# Port_Headers.net
KiCad netlist of a schematic drawn in Altium Designer
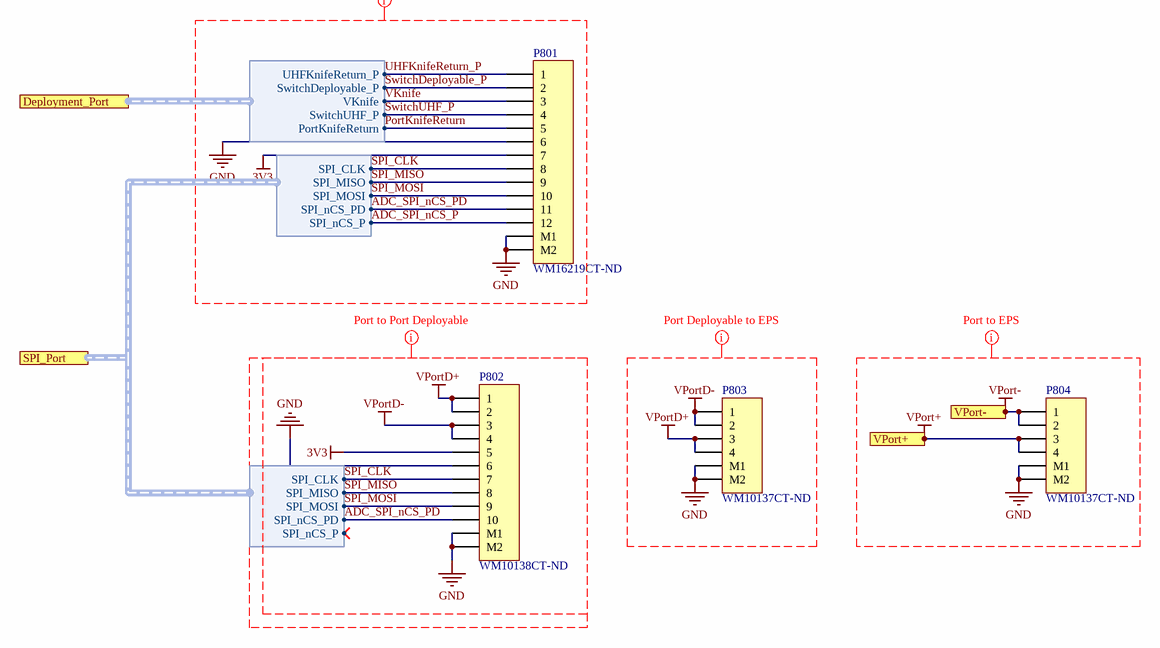
[diagram p0: Port_Headers.SchDoc]

(export (version "E")
  (design (tool "Eeschema 10.0.6"))
  (components
    (comp (ref "P801")
      (value "WM16219CT-ND")
      (footprint "MOLX-5040501291")
      (description "CONN HEADER SMD R/A 12POS 1.5MM")
      (fields
        (field (name "PART NUMBER") "71")
        (field (name "MANUFACTURER PART NUMBER") "5040501291")
        (field (name "PUBLISHER") "Altium Limited")
      )
      (libsource (lib "Database") (part "Header 14"))
    )
    (comp (ref "P802")
      (value "WM10138CT-ND")
      (footprint "MOLX-5040501091")
      (description "CONN HEADER SMD R/A 10POS 1.5MM")
      (fields
        (field (name "PART NUMBER") "69")
        (field (name "MANUFACTURER PART NUMBER") "5040501091")
        (field (name "PUBLISHER") "Altium Limited")
      )
      (libsource (lib "Database") (part "Header 12"))
    )
    (comp (ref "P803")
      (value "WM10137CT-ND")
      (footprint "MOLX-5040500491")
      (description "CONN HEADER SMD R/A 4POS 1.5MM")
      (fields
        (field (name "PART NUMBER") "63")
        (field (name "MANUFACTURER PART NUMBER") "5040500491")
        (field (name "PUBLISHER") "Altium Limited")
      )
      (libsource (lib "Database") (part "Header 6"))
    )
    (comp (ref "P804")
      (value "WM10137CT-ND")
      (footprint "MOLX-5040500491")
      (description "CONN HEADER SMD R/A 4POS 1.5MM")
      (fields
        (field (name "PART NUMBER") "63")
        (field (name "MANUFACTURER PART NUMBER") "5040500491")
        (field (name "PUBLISHER") "Altium Limited")
      )
      (libsource (lib "Database") (part "Header 6"))
    )
  )
  (nets
    (net (code "3") (name "/ADC_SPI_nCS_P") (class "Default")
      (node (ref "P801") (pin "12") (pinfunction "12_12") (pintype "passive"))
    )
    (net (code "4") (name "/ADC_SPI_nCS_PD") (class "Default")
      (node (ref "P801") (pin "11") (pinfunction "11_11") (pintype "passive"))
      (node (ref "P802") (pin "10") (pinfunction "10_10") (pintype "passive"))
    )
    (net (code "5") (name "/PortKnifeReturn") (class "Default")
      (node (ref "P801") (pin "5") (pinfunction "5_5") (pintype "passive"))
    )
    (net (code "6") (name "/SPI_CLK") (class "Default")
      (node (ref "P801") (pin "8") (pinfunction "8_8") (pintype "passive"))
      (node (ref "P802") (pin "7") (pinfunction "7_7") (pintype "passive"))
    )
    (net (code "7") (name "/SPI_MISO") (class "Default")
      (node (ref "P801") (pin "9") (pinfunction "9_9") (pintype "passive"))
      (node (ref "P802") (pin "8") (pinfunction "8_8") (pintype "passive"))
    )
    (net (code "8") (name "/SPI_MOSI") (class "Default")
      (node (ref "P801") (pin "10") (pinfunction "10_10") (pintype "passive"))
      (node (ref "P802") (pin "9") (pinfunction "9_9") (pintype "passive"))
    )
    (net (code "9") (name "/SwitchDeployable_P") (class "Default")
      (node (ref "P801") (pin "2") (pinfunction "2_2") (pintype "passive"))
    )
    (net (code "10") (name "/SwitchUHF_P") (class "Default")
      (node (ref "P801") (pin "4") (pinfunction "4_4") (pintype "passive"))
    )
    (net (code "11") (name "/UHFKnifeReturn_P") (class "Default")
      (node (ref "P801") (pin "1") (pinfunction "1_1") (pintype "passive"))
    )
    (net (code "12") (name "/VKnife") (class "Default")
      (node (ref "P801") (pin "3") (pinfunction "3_3") (pintype "passive"))
    )
    (net (code "15") (name "3V3") (class "Default")
      (node (ref "P801") (pin "7") (pinfunction "7_7") (pintype "passive"))
      (node (ref "P802") (pin "5") (pinfunction "5_5") (pintype "passive"))
    )
    (net (code "16") (name "GND") (class "Default")
      (node (ref "P801") (pin "6") (pinfunction "6_6") (pintype "passive"))
      (node (ref "P801") (pin "M1") (pinfunction "M1_M1") (pintype "passive"))
      (node (ref "P801") (pin "M2") (pinfunction "M2_M2") (pintype "passive"))
      (node (ref "P802") (pin "6") (pinfunction "6_6") (pintype "passive"))
      (node (ref "P802") (pin "M1") (pinfunction "M1_M1") (pintype "passive"))
      (node (ref "P802") (pin "M2") (pinfunction "M2_M2") (pintype "passive"))
      (node (ref "P803") (pin "M1") (pinfunction "M1_M1") (pintype "passive"))
      (node (ref "P803") (pin "M2") (pinfunction "M2_M2") (pintype "passive"))
      (node (ref "P804") (pin "M1") (pinfunction "M1_M1") (pintype "passive"))
      (node (ref "P804") (pin "M2") (pinfunction "M2_M2") (pintype "passive"))
    )
    (net (code "17") (name "VPort+") (class "Default")
      (node (ref "P804") (pin "3") (pinfunction "3_3") (pintype "passive"))
      (node (ref "P804") (pin "4") (pinfunction "4_4") (pintype "passive"))
    )
    (net (code "18") (name "VPort-") (class "Default")
      (node (ref "P804") (pin "1") (pinfunction "1_1") (pintype "passive"))
      (node (ref "P804") (pin "2") (pinfunction "2_2") (pintype "passive"))
    )
    (net (code "19") (name "VPortD+") (class "Default")
      (node (ref "P802") (pin "1") (pinfunction "1_1") (pintype "passive"))
      (node (ref "P802") (pin "2") (pinfunction "2_2") (pintype "passive"))
      (node (ref "P803") (pin "3") (pinfunction "3_3") (pintype "passive"))
      (node (ref "P803") (pin "4") (pinfunction "4_4") (pintype "passive"))
    )
    (net (code "20") (name "VPortD-") (class "Default")
      (node (ref "P802") (pin "3") (pinfunction "3_3") (pintype "passive"))
      (node (ref "P802") (pin "4") (pinfunction "4_4") (pintype "passive"))
      (node (ref "P803") (pin "1") (pinfunction "1_1") (pintype "passive"))
      (node (ref "P803") (pin "2") (pinfunction "2_2") (pintype "passive"))
    )
  )
)
